# Peripherals.net
KiCad netlist of a schematic drawn in Altium Designer
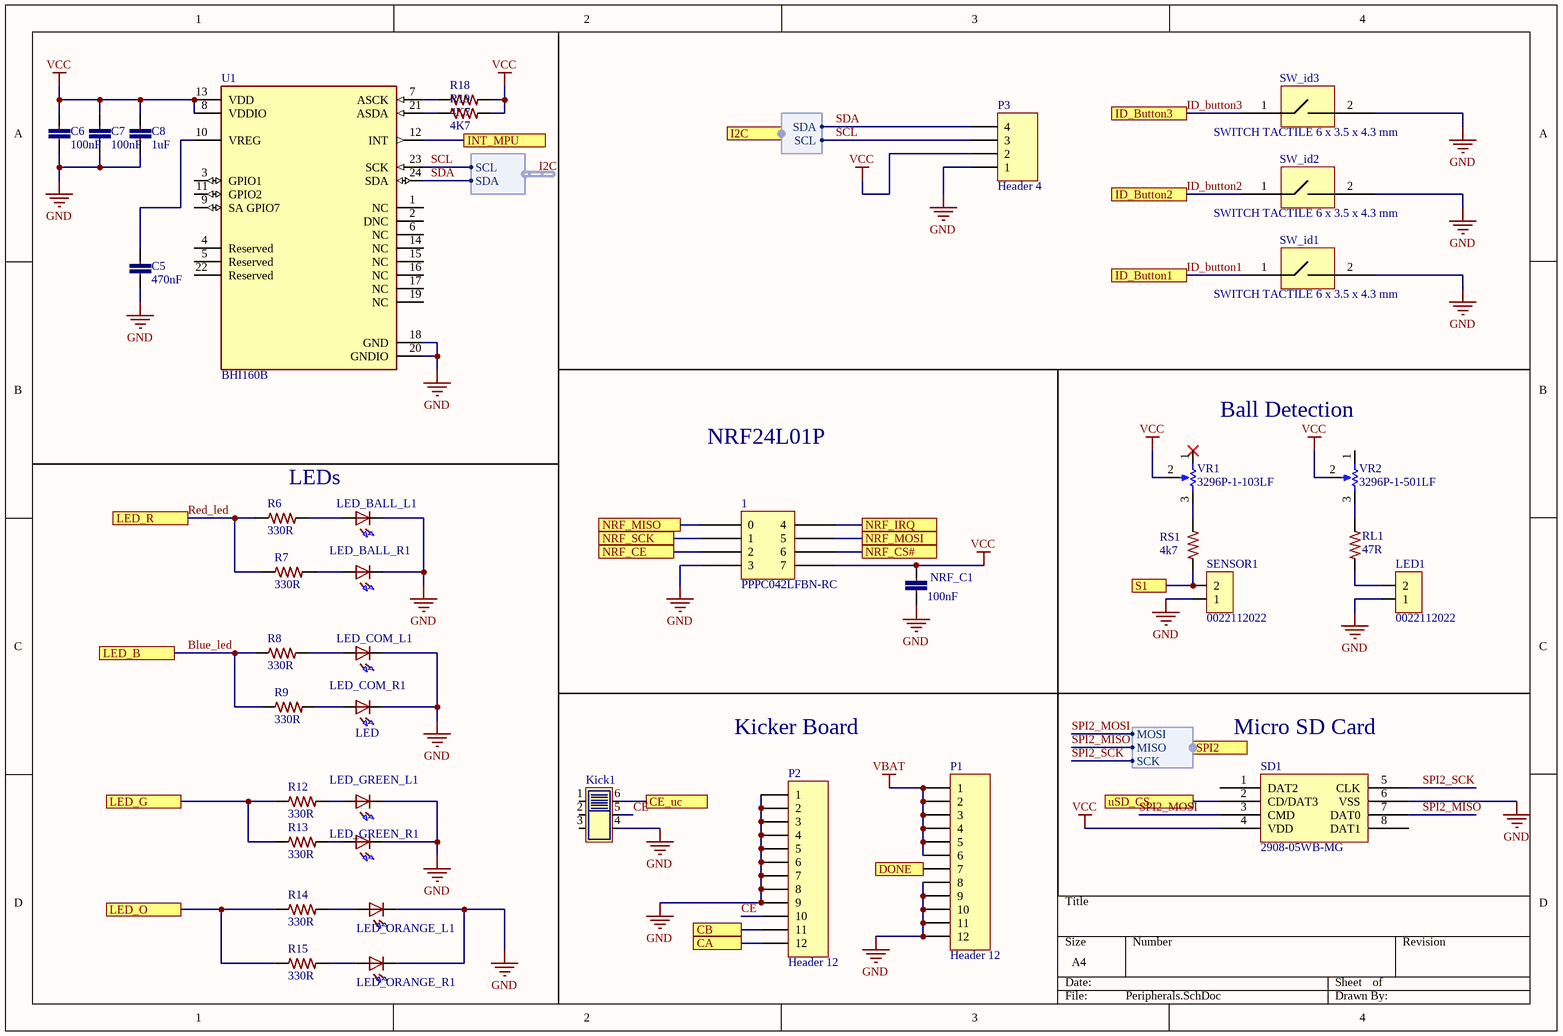
[diagram p0: Peripherals.SchDoc]

(export (version "E")
  (design (tool "Eeschema 10.0.6"))
  (components
    (comp (ref "1")
      (value "PPPC042LFBN-RC")
      (footprint "04x02_Conector_Female")
      (description "8 Position Header Connector 0.100\" (2.54mm) Through Hole Gold")
      (libsource (lib "Schlib1") (part "04x02_Conector_Female"))
    )
    (comp (ref "C5")
      (value "470nF")
      (footprint "0402-CAP")
      (description "CAP CER 0402 470nF 25V X5R")
      (fields (field (name "PART NO") "C1005X5R1E474K050"))
      (libsource (lib "IMBEL") (part "CAPACITOR"))
    )
    (comp (ref "C6")
      (value "100nF")
      (footprint "0402-CAP")
      (description "CAP CER 0.1UF 10V 20% X5R 0402")
      (fields (field (name "PART NO") "VJ0402V104ZXQPBC"))
      (libsource (lib "IMBEL") (part "CAPACITOR"))
    )
    (comp (ref "C7")
      (value "100nF")
      (footprint "0402-CAP")
      (description "CAP CER 0.1UF 10V 20% X5R 0402")
      (fields (field (name "PART NO") "VJ0402V104ZXQPBC"))
      (libsource (lib "IMBEL") (part "CAPACITOR"))
    )
    (comp (ref "C8")
      (value "1uF")
      (footprint "0402-CAP")
      (description "CAP CER 1UF 6.3V 10% X5R 0402")
      (fields (field (name "PART NO") "JMK105BJ105KV-F"))
      (libsource (lib "IMBEL") (part "CAPACITOR"))
    )
    (comp (ref "Kick1")
      (value "JS202011SCQN")
      (footprint "SOP250P750X350-6N")
      (description "SWITCH SLIDE DPDT 300MA 6V")
      (libsource (lib "") (part "Component_1_1"))
    )
    (comp (ref "LED1")
      (value "0022112022")
      (footprint "02x01_Conector_Male")
      (description "CONN HEADER 2POS .100 VERT GOLD")
      (libsource (lib "Schlib1") (part "02x01_Conector_Male"))
    )
    (comp (ref "LED_BALL_L1")
      (value "LED")
      (footprint "LED-5MM-PCB")
      (description "LED 5MM PTH")
      (libsource (lib "IMBEL") (part "LED"))
    )
    (comp (ref "LED_BALL_R1")
      (value "LED")
      (footprint "LED-5MM-PCB")
      (description "LED 5MM PTH")
      (libsource (lib "IMBEL") (part "LED"))
    )
    (comp (ref "LED_COM_L1")
      (value "LED")
      (footprint "LED-5MM-PCB")
      (description "LED 5MM PTH")
      (libsource (lib "IMBEL") (part "LED"))
    )
    (comp (ref "LED_COM_R1")
      (value "LED")
      (footprint "LED-5MM-PCB")
      (description "LED 5MM PTH")
      (libsource (lib "IMBEL") (part "LED"))
    )
    (comp (ref "LED_GREEN_L1")
      (value "LED")
      (footprint "LED-5MM-PCB")
      (description "LED 5MM PTH")
      (libsource (lib "IMBEL") (part "LED"))
    )
    (comp (ref "LED_GREEN_R1")
      (value "LED")
      (footprint "LED-5MM-PCB")
      (description "LED 5MM PTH")
      (libsource (lib "IMBEL") (part "LED"))
    )
    (comp (ref "LED_ORANGE_L1")
      (value "LED")
      (footprint "LED-5MM-PCB")
      (description "LED 5MM PTH")
      (libsource (lib "IMBEL") (part "LED"))
    )
    (comp (ref "LED_ORANGE_R1")
      (value "LED")
      (footprint "LED-5MM-PCB")
      (description "LED 5MM PTH")
      (libsource (lib "IMBEL") (part "LED"))
    )
    (comp (ref "NRF_C1")
      (value "100nF")
      (footprint "0402-CAP")
      (description "CAP CER 0.1UF 10V 20% X5R 0402")
      (fields (field (name "PART NO") "VJ0402V104ZXQPBC"))
      (libsource (lib "IMBEL") (part "CC0402-100nF-A.12"))
    )
    (comp (ref "P1")
      (value "Header 12")
      (footprint "HDR1X12")
      (description "Header, 12-Pin")
      (fields (field (name "PUBLISHER") "Altium Limited"))
      (libsource (lib "Miscellaneous Connectors") (part "Header 12"))
    )
    (comp (ref "P2")
      (value "Header 12")
      (footprint "HDR1X12")
      (description "Header, 12-Pin")
      (fields (field (name "PUBLISHER") "Altium Limited"))
      (libsource (lib "Miscellaneous Connectors") (part "Header 12"))
    )
    (comp (ref "P3")
      (value "Header 4")
      (footprint "HDR1X4")
      (description "Header, 4-Pin")
      (fields (field (name "PUBLISHER") "Altium Limited"))
      (libsource (lib "Miscellaneous Connectors") (part "Header 4"))
    )
    (comp (ref "R6")
      (value "330R")
      (footprint "0402-RES-HD")
      (description "RES 330 OHM 1/10W 1% 0402 SMD")
      (fields (field (name "PART NO") "ERJ-2RKF3300X"))
      (libsource (lib "IMBEL") (part "RESISTOR"))
    )
    (comp (ref "R7")
      (value "330R")
      (footprint "0402-RES-HD")
      (description "RES 330 OHM 1/10W 1% 0402 SMD")
      (fields (field (name "PART NO") "ERJ-2RKF3300X"))
      (libsource (lib "IMBEL") (part "RESISTOR"))
    )
    (comp (ref "R8")
      (value "330R")
      (footprint "0402-RES-HD")
      (description "RES 330 OHM 1/10W 1% 0402 SMD")
      (fields (field (name "PART NO") "ERJ-2RKF3300X"))
      (libsource (lib "IMBEL") (part "RESISTOR"))
    )
    (comp (ref "R9")
      (value "330R")
      (footprint "0402-RES-HD")
      (description "RES 330 OHM 1/10W 1% 0402 SMD")
      (fields (field (name "PART NO") "ERJ-2RKF3300X"))
      (libsource (lib "IMBEL") (part "RESISTOR"))
    )
    (comp (ref "R12")
      (value "330R")
      (footprint "0402-RES-HD")
      (description "RES 330 OHM 1/10W 1% 0402 SMD")
      (fields (field (name "PART NO") "ERJ-2RKF3300X"))
      (libsource (lib "IMBEL") (part "RESISTOR"))
    )
    (comp (ref "R13")
      (value "330R")
      (footprint "0402-RES-HD")
      (description "RES 330 OHM 1/10W 1% 0402 SMD")
      (fields (field (name "PART NO") "ERJ-2RKF3300X"))
      (libsource (lib "IMBEL") (part "RESISTOR"))
    )
    (comp (ref "R14")
      (value "330R")
      (footprint "0402-RES-HD")
      (description "RES 330 OHM 1/10W 1% 0402 SMD")
      (fields (field (name "PART NO") "ERJ-2RKF3300X"))
      (libsource (lib "IMBEL") (part "RESISTOR"))
    )
    (comp (ref "R15")
      (value "330R")
      (footprint "0402-RES-HD")
      (description "RES 330 OHM 1/10W 1% 0402 SMD")
      (fields (field (name "PART NO") "ERJ-2RKF3300X"))
      (libsource (lib "IMBEL") (part "RESISTOR"))
    )
    (comp (ref "R18")
      (value "4K7")
      (footprint "0805-RES")
      (description "RES SMD 4.7K OHM 1% 1/8W 0805")
      (fields (field (name "PART NO") "CRCW08054K70FKEA"))
      (libsource (lib "IMBEL") (part "RESISTOR"))
    )
    (comp (ref "R19")
      (value "4K7")
      (footprint "0805-RES")
      (description "RES SMD 4.7K OHM 1% 1/8W 0805")
      (fields (field (name "PART NO") "CRCW08054K70FKEA"))
      (libsource (lib "IMBEL") (part "RESISTOR"))
    )
    (comp (ref "RL1")
      (value "47R")
      (footprint "0402-RES-HD")
      (description "RES 47 OHM 1/10W 1% 0402 SMD")
      (fields (field (name "PART NO") "ERJ-2RKF1000X"))
      (libsource (lib "IMBEL") (part "RESISTOR"))
    )
    (comp (ref "RS1")
      (value "4k7")
      (footprint "0402-RES-HD")
      (description "RES 4k7 OHM 1/10W 1% 0402 SMD")
      (fields (field (name "PART NO") "ERJ-2RKF3300X"))
      (libsource (lib "IMBEL") (part "RESISTOR"))
    )
    (comp (ref "SD1")
      (value "2908-05WB-MG")
      (footprint "New footprint 1")
      (description "CONN MICRO SD CARD PUSH-PUSH R/A")
      (libsource (lib "IMBEL") (part "SD-CON-SCH"))
    )
    (comp (ref "SENSOR1")
      (value "0022112022")
      (footprint "02x01_Conector_Male")
      (description "CONN HEADER 2POS .100 VERT GOLD")
      (libsource (lib "Schlib1") (part "02x01_Conector_Male"))
    )
    (comp (ref "SW_id1")
      (value "SWITCH TACTILE 6 x 3.5 x 4.3 mm")
      (footprint "PCBComponent")
      (description "GRAYHILL TACT,GW,6X3.5,1800T&R,LF Eight, 160g Operating Force, Gull Wing, RoHS Compliant")
      (fields (field (name "PART NO") "95C04A3GWRT"))
      (libsource (lib "IMBEL") (part "Component_1"))
    )
    (comp (ref "SW_id2")
      (value "SWITCH TACTILE 6 x 3.5 x 4.3 mm")
      (footprint "PCBComponent")
      (description "GRAYHILL TACT,GW,6X3.5,1800T&R,LF Eight, 160g Operating Force, Gull Wing, RoHS Compliant")
      (fields (field (name "PART NO") "95C04A3GWRT"))
      (libsource (lib "IMBEL") (part "Component_1"))
    )
    (comp (ref "SW_id3")
      (value "SWITCH TACTILE 6 x 3.5 x 4.3 mm")
      (footprint "PCBComponent")
      (description "GRAYHILL TACT,GW,6X3.5,1800T&R,LF Eight, 160g Operating Force, Gull Wing, RoHS Compliant")
      (fields (field (name "PART NO") "95C04A3GWRT"))
      (libsource (lib "IMBEL") (part "Component_1"))
    )
    (comp (ref "U1")
      (value "BHI160B")
      (footprint "FP-BHI160B-MFG")
      (description "IMU ACCEL/GYRO 3-AXIS I2C 24LGA")
      (fields
        (field (name "OCTOPART") "https://octopart.com/bhi160b-bosch+sensortec-108216126")
        (field (name "MANUFACTURER") "Bosch Sensortec")
      )
      (libsource (lib "Altium Content Vault") (part "2d8cd2e68e3e323d24208bb39551349"))
    )
    (comp (ref "VR1")
      (value "3296P-1-103LF")
      (footprint "pcblib1:3296P")
      (description "Trimmer;  Cermet;  Rest 10 Kilohms;  PCB;  25 Turns;  Pwr-Rtg 0.5W")
      (fields (field (name "MANUFACTURER") "Bourns") (field (name "TOLERANCE") "10%"))
      (libsource (lib "Schlib1") (part "3296P-1-103LF"))
    )
    (comp (ref "VR2")
      (value "3296P-1-501LF")
      (footprint "PcbLib1:3296P")
      (description "Res Cermet Trimmer 500 Ohm 10% 1/2W 25(Elec)Turn 2.19mm (9.53 X 11.55 X 4.83mm) Pin Thru-Hole Tube")
      (fields (field (name "MANUFACTURER") "Bourns") (field (name "TOLERANCE") "10%"))
      (libsource (lib "Schlib1") (part "3296P-1-501LF"))
    )
  )
  (nets
    (net (code "4") (name "/Blue_led") (class "Default")
      (node (ref "R8") (pin "1") (pinfunction "1_1") (pintype "passive"))
      (node (ref "R9") (pin "1") (pinfunction "1_1") (pintype "passive"))
    )
    (net (code "5") (name "/CA") (class "Default")
      (node (ref "P2") (pin "12") (pinfunction "12_12") (pintype "passive"))
    )
    (net (code "6") (name "/CB") (class "Default")
      (node (ref "P2") (pin "11") (pinfunction "11_11") (pintype "passive"))
    )
    (net (code "7") (name "/CE") (class "Default")
      (node (ref "Kick1") (pin "5") (pintype "passive"))
      (node (ref "P2") (pin "10") (pinfunction "10_10") (pintype "passive"))
    )
    (net (code "8") (name "/CE_uc") (class "Default") (node (ref "Kick1") (pin "6") (pintype "passive")))
    (net (code "9") (name "/DONE") (class "Default")
      (node (ref "P1") (pin "7") (pinfunction "7_7") (pintype "passive"))
    )
    (net (code "11") (name "/ID_button1") (class "Default")
      (node (ref "SW_id1") (pin "1") (pinfunction "1_1") (pintype "passive"))
    )
    (net (code "12") (name "/ID_button2") (class "Default")
      (node (ref "SW_id2") (pin "1") (pinfunction "1_1") (pintype "passive"))
    )
    (net (code "13") (name "/ID_button3") (class "Default")
      (node (ref "SW_id3") (pin "1") (pinfunction "1_1") (pintype "passive"))
    )
    (net (code "14") (name "/INT_MPU") (class "Default")
      (node (ref "U1") (pin "12") (pinfunction "INT_12") (pintype "output"))
    )
    (net (code "15") (name "/LED_G") (class "Default")
      (node (ref "R12") (pin "1") (pinfunction "1_1") (pintype "passive"))
      (node (ref "R13") (pin "1") (pinfunction "1_1") (pintype "passive"))
    )
    (net (code "16") (name "/LED_O") (class "Default")
      (node (ref "R14") (pin "1") (pinfunction "1_1") (pintype "passive"))
      (node (ref "R15") (pin "1") (pinfunction "1_1") (pintype "passive"))
    )
    (net (code "17") (name "/NRF_CE") (class "Default")
      (node (ref "1") (pin "2") (pinfunction "2_2") (pintype "passive"))
    )
    (net (code "18") (name "/NRF_CS#") (class "Default")
      (node (ref "1") (pin "6") (pinfunction "6_6") (pintype "passive"))
    )
    (net (code "19") (name "/NRF_IRQ") (class "Default")
      (node (ref "1") (pin "4") (pinfunction "4_4") (pintype "passive"))
    )
    (net (code "20") (name "/NRF_MISO") (class "Default")
      (node (ref "1") (pin "0") (pinfunction "0_0") (pintype "passive"))
    )
    (net (code "21") (name "/NRF_MOSI") (class "Default")
      (node (ref "1") (pin "5") (pinfunction "5_5") (pintype "passive"))
    )
    (net (code "22") (name "/NRF_SCK") (class "Default")
      (node (ref "1") (pin "1") (pinfunction "1_1") (pintype "passive"))
    )
    (net (code "23") (name "/Red_led") (class "Default")
      (node (ref "R6") (pin "1") (pinfunction "1_1") (pintype "passive"))
      (node (ref "R7") (pin "1") (pinfunction "1_1") (pintype "passive"))
    )
    (net (code "24") (name "/S1") (class "Default")
      (node (ref "RS1") (pin "1") (pinfunction "1_1") (pintype "passive"))
      (node (ref "SENSOR1") (pin "2") (pinfunction "2_2") (pintype "passive"))
    )
    (net (code "25") (name "/SCL") (class "Default")
      (node (ref "P3") (pin "3") (pinfunction "3_3") (pintype "passive"))
      (node (ref "U1") (pin "23") (pinfunction "SCK_23") (pintype "input"))
    )
    (net (code "26") (name "/SDA") (class "Default")
      (node (ref "P3") (pin "4") (pinfunction "4_4") (pintype "passive"))
      (node (ref "U1") (pin "24") (pinfunction "SDA_24") (pintype "bidirectional"))
    )
    (net (code "27") (name "/SPI2_MISO") (class "Default")
      (node (ref "SD1") (pin "7") (pinfunction "DAT0_7") (pintype "passive"))
    )
    (net (code "28") (name "/SPI2_MOSI") (class "Default")
      (node (ref "SD1") (pin "3") (pinfunction "CMD_3") (pintype "passive"))
    )
    (net (code "29") (name "/SPI2_SCK") (class "Default")
      (node (ref "SD1") (pin "5") (pinfunction "CLK_5") (pintype "passive"))
    )
    (net (code "30") (name "/uSD_CS") (class "Default")
      (node (ref "SD1") (pin "2") (pinfunction "CD/DAT3_2") (pintype "passive"))
    )
    (net (code "32") (name "GND") (class "Default")
      (node (ref "1") (pin "3") (pinfunction "3_3") (pintype "passive"))
      (node (ref "C5") (pin "2") (pinfunction "2_2") (pintype "passive"))
      (node (ref "C6") (pin "2") (pinfunction "2_2") (pintype "passive"))
      (node (ref "C7") (pin "2") (pinfunction "2_2") (pintype "passive"))
      (node (ref "C8") (pin "2") (pinfunction "2_2") (pintype "passive"))
      (node (ref "Kick1") (pin "4") (pintype "passive"))
      (node (ref "LED1") (pin "1") (pinfunction "1_1") (pintype "passive"))
      (node (ref "LED_BALL_L1") (pin "1") (pinfunction "K_1") (pintype "passive"))
      (node (ref "LED_BALL_R1") (pin "1") (pinfunction "K_1") (pintype "passive"))
      (node (ref "LED_COM_L1") (pin "1") (pinfunction "K_1") (pintype "passive"))
      (node (ref "LED_COM_R1") (pin "1") (pinfunction "K_1") (pintype "passive"))
      (node (ref "LED_GREEN_L1") (pin "1") (pinfunction "K_1") (pintype "passive"))
      (node (ref "LED_GREEN_R1") (pin "1") (pinfunction "K_1") (pintype "passive"))
      (node (ref "LED_ORANGE_L1") (pin "1") (pinfunction "K_1") (pintype "passive"))
      (node (ref "LED_ORANGE_R1") (pin "1") (pinfunction "K_1") (pintype "passive"))
      (node (ref "NRF_C1") (pin "2") (pinfunction "2_2") (pintype "passive"))
      (node (ref "P1") (pin "10") (pinfunction "10_10") (pintype "passive"))
      (node (ref "P1") (pin "11") (pinfunction "11_11") (pintype "passive"))
      (node (ref "P1") (pin "12") (pinfunction "12_12") (pintype "passive"))
      (node (ref "P1") (pin "8") (pinfunction "8_8") (pintype "passive"))
      (node (ref "P1") (pin "9") (pinfunction "9_9") (pintype "passive"))
      (node (ref "P2") (pin "1") (pinfunction "1_1") (pintype "passive"))
      (node (ref "P2") (pin "2") (pinfunction "2_2") (pintype "passive"))
      (node (ref "P2") (pin "3") (pinfunction "3_3") (pintype "passive"))
      (node (ref "P2") (pin "4") (pinfunction "4_4") (pintype "passive"))
      (node (ref "P2") (pin "5") (pinfunction "5_5") (pintype "passive"))
      (node (ref "P2") (pin "6") (pinfunction "6_6") (pintype "passive"))
      (node (ref "P2") (pin "7") (pinfunction "7_7") (pintype "passive"))
      (node (ref "P2") (pin "8") (pinfunction "8_8") (pintype "passive"))
      (node (ref "P2") (pin "9") (pinfunction "9_9") (pintype "passive"))
      (node (ref "P3") (pin "1") (pinfunction "1_1") (pintype "passive"))
      (node (ref "SD1") (pin "6") (pinfunction "VSS_6") (pintype "passive"))
      (node (ref "SENSOR1") (pin "1") (pinfunction "1_1") (pintype "passive"))
      (node (ref "SW_id1") (pin "2") (pinfunction "2_2") (pintype "passive"))
      (node (ref "SW_id2") (pin "2") (pinfunction "2_2") (pintype "passive"))
      (node (ref "SW_id3") (pin "2") (pinfunction "2_2") (pintype "passive"))
      (node (ref "U1") (pin "18") (pinfunction "GND_18") (pintype "power_in"))
      (node (ref "U1") (pin "20") (pinfunction "GNDIO_20") (pintype "power_in"))
    )
    (net (code "33") (name "Net-(LED1-Pad2)") (class "Default")
      (node (ref "LED1") (pin "2") (pinfunction "2_2") (pintype "passive"))
      (node (ref "RL1") (pin "2") (pinfunction "2_2") (pintype "passive"))
    )
    (net (code "34") (name "Net-(LED_BALL_L1-A)") (class "Default")
      (node (ref "LED_BALL_L1") (pin "2") (pinfunction "A_2") (pintype "passive"))
      (node (ref "R6") (pin "2") (pinfunction "2_2") (pintype "passive"))
    )
    (net (code "35") (name "Net-(LED_BALL_R1-A)") (class "Default")
      (node (ref "LED_BALL_R1") (pin "2") (pinfunction "A_2") (pintype "passive"))
      (node (ref "R7") (pin "2") (pinfunction "2_2") (pintype "passive"))
    )
    (net (code "36") (name "Net-(LED_COM_L1-A)") (class "Default")
      (node (ref "LED_COM_L1") (pin "2") (pinfunction "A_2") (pintype "passive"))
      (node (ref "R8") (pin "2") (pinfunction "2_2") (pintype "passive"))
    )
    (net (code "37") (name "Net-(LED_COM_R1-A)") (class "Default")
      (node (ref "LED_COM_R1") (pin "2") (pinfunction "A_2") (pintype "passive"))
      (node (ref "R9") (pin "2") (pinfunction "2_2") (pintype "passive"))
    )
    (net (code "38") (name "Net-(LED_GREEN_L1-A)") (class "Default")
      (node (ref "LED_GREEN_L1") (pin "2") (pinfunction "A_2") (pintype "passive"))
      (node (ref "R12") (pin "2") (pinfunction "2_2") (pintype "passive"))
    )
    (net (code "39") (name "Net-(LED_GREEN_R1-A)") (class "Default")
      (node (ref "LED_GREEN_R1") (pin "2") (pinfunction "A_2") (pintype "passive"))
      (node (ref "R13") (pin "2") (pinfunction "2_2") (pintype "passive"))
    )
    (net (code "40") (name "Net-(LED_ORANGE_L1-A)") (class "Default")
      (node (ref "LED_ORANGE_L1") (pin "2") (pinfunction "A_2") (pintype "passive"))
      (node (ref "R14") (pin "2") (pinfunction "2_2") (pintype "passive"))
    )
    (net (code "41") (name "Net-(LED_ORANGE_R1-A)") (class "Default")
      (node (ref "LED_ORANGE_R1") (pin "2") (pinfunction "A_2") (pintype "passive"))
      (node (ref "R15") (pin "2") (pinfunction "2_2") (pintype "passive"))
    )
    (net (code "42") (name "Net-(U1-ASCK)") (class "Default")
      (node (ref "R18") (pin "1") (pinfunction "1_1") (pintype "passive"))
      (node (ref "U1") (pin "7") (pinfunction "ASCK_7") (pintype "input"))
    )
    (net (code "43") (name "Net-(U1-ASDA)") (class "Default")
      (node (ref "R19") (pin "1") (pinfunction "1_1") (pintype "passive"))
      (node (ref "U1") (pin "21") (pinfunction "ASDA_21") (pintype "input"))
    )
    (net (code "44") (name "Net-(U1-VREG)") (class "Default")
      (node (ref "C5") (pin "1") (pinfunction "1_1") (pintype "passive"))
      (node (ref "U1") (pin "10") (pinfunction "VREG_10") (pintype "passive"))
    )
    (net (code "45") (name "Net-(VR1-CW)") (class "Default")
      (node (ref "RS1") (pin "2") (pinfunction "2_2") (pintype "passive"))
      (node (ref "VR1") (pin "3") (pinfunction "CW_3") (pintype "passive"))
    )
    (net (code "46") (name "Net-(VR2-CW)") (class "Default")
      (node (ref "RL1") (pin "1") (pinfunction "1_1") (pintype "passive"))
      (node (ref "VR2") (pin "3") (pinfunction "CW_3") (pintype "passive"))
    )
    (net (code "47") (name "VBAT") (class "Default")
      (node (ref "P1") (pin "1") (pinfunction "1_1") (pintype "passive"))
      (node (ref "P1") (pin "2") (pinfunction "2_2") (pintype "passive"))
      (node (ref "P1") (pin "3") (pinfunction "3_3") (pintype "passive"))
      (node (ref "P1") (pin "4") (pinfunction "4_4") (pintype "passive"))
      (node (ref "P1") (pin "5") (pinfunction "5_5") (pintype "passive"))
      (node (ref "P1") (pin "6") (pinfunction "6_6") (pintype "passive"))
    )
    (net (code "48") (name "VCC") (class "Default")
      (node (ref "1") (pin "7") (pinfunction "7_7") (pintype "passive"))
      (node (ref "C6") (pin "1") (pinfunction "1_1") (pintype "passive"))
      (node (ref "C7") (pin "1") (pinfunction "1_1") (pintype "passive"))
      (node (ref "C8") (pin "1") (pinfunction "1_1") (pintype "passive"))
      (node (ref "NRF_C1") (pin "1") (pinfunction "1_1") (pintype "passive"))
      (node (ref "P3") (pin "2") (pinfunction "2_2") (pintype "passive"))
      (node (ref "R18") (pin "2") (pinfunction "2_2") (pintype "passive"))
      (node (ref "R19") (pin "2") (pinfunction "2_2") (pintype "passive"))
      (node (ref "SD1") (pin "4") (pinfunction "VDD_4") (pintype "passive"))
      (node (ref "U1") (pin "13") (pinfunction "VDD_13") (pintype "power_in"))
      (node (ref "U1") (pin "8") (pinfunction "VDDIO_8") (pintype "power_in"))
      (node (ref "VR1") (pin "2") (pinfunction "Wiper_2") (pintype "passive"))
      (node (ref "VR2") (pin "2") (pinfunction "Wiper_2") (pintype "passive"))
    )
    (net (code "49") (name "unconnected-(Kick1-Pad1)") (class "Default")
      (node (ref "Kick1") (pin "1") (pintype "passive"))
    )
    (net (code "50") (name "unconnected-(Kick1-Pad2)") (class "Default")
      (node (ref "Kick1") (pin "2") (pintype "passive"))
    )
    (net (code "51") (name "unconnected-(Kick1-Pad3)") (class "Default")
      (node (ref "Kick1") (pin "3") (pintype "passive"))
    )
    (net (code "52") (name "unconnected-(SD1-DAT1-Pad8)") (class "Default")
      (node (ref "SD1") (pin "8") (pinfunction "DAT1_8") (pintype "passive"))
    )
    (net (code "53") (name "unconnected-(SD1-DAT2-Pad1)") (class "Default")
      (node (ref "SD1") (pin "1") (pinfunction "DAT2_1") (pintype "passive"))
    )
    (net (code "54") (name "unconnected-(U1-DNC-Pad2)") (class "Default")
      (node (ref "U1") (pin "2") (pinfunction "DNC_2") (pintype "passive"))
    )
    (net (code "55") (name "unconnected-(U1-GPIO1-Pad3)") (class "Default")
      (node (ref "U1") (pin "3") (pinfunction "GPIO1_3") (pintype "bidirectional"))
    )
    (net (code "56") (name "unconnected-(U1-GPIO2-Pad11)") (class "Default")
      (node (ref "U1") (pin "11") (pinfunction "GPIO2_11") (pintype "bidirectional"))
    )
    (net (code "57") (name "unconnected-(U1-NC-Pad1)") (class "Default")
      (node (ref "U1") (pin "1") (pinfunction "NC_1") (pintype "passive"))
    )
    (net (code "58") (name "unconnected-(U1-NC-Pad6)") (class "Default")
      (node (ref "U1") (pin "6") (pinfunction "NC_6") (pintype "passive"))
    )
    (net (code "59") (name "unconnected-(U1-NC-Pad14)") (class "Default")
      (node (ref "U1") (pin "14") (pinfunction "NC_14") (pintype "passive"))
    )
    (net (code "60") (name "unconnected-(U1-NC-Pad15)") (class "Default")
      (node (ref "U1") (pin "15") (pinfunction "NC_15") (pintype "passive"))
    )
    (net (code "61") (name "unconnected-(U1-NC-Pad16)") (class "Default")
      (node (ref "U1") (pin "16") (pinfunction "NC_16") (pintype "passive"))
    )
    (net (code "62") (name "unconnected-(U1-NC-Pad17)") (class "Default")
      (node (ref "U1") (pin "17") (pinfunction "NC_17") (pintype "passive"))
    )
    (net (code "63") (name "unconnected-(U1-NC-Pad19)") (class "Default")
      (node (ref "U1") (pin "19") (pinfunction "NC_19") (pintype "passive"))
    )
    (net (code "64") (name "unconnected-(U1-Reserved-Pad4)") (class "Default")
      (node (ref "U1") (pin "4") (pinfunction "Reserved_4") (pintype "passive"))
    )
    (net (code "65") (name "unconnected-(U1-Reserved-Pad5)") (class "Default")
      (node (ref "U1") (pin "5") (pinfunction "Reserved_5") (pintype "passive"))
    )
    (net (code "66") (name "unconnected-(U1-Reserved-Pad22)") (class "Default")
      (node (ref "U1") (pin "22") (pinfunction "Reserved_22") (pintype "passive"))
    )
    (net (code "67") (name "unconnected-(U1-SA_GPIO7-Pad9)") (class "Default")
      (node (ref "U1") (pin "9") (pinfunction "SA_GPIO7_9") (pintype "bidirectional"))
    )
    (net (code "68") (name "unconnected-(VR1-CCW-Pad1)") (class "Default")
      (node (ref "VR1") (pin "1") (pinfunction "CCW_1") (pintype "passive+no_connect"))
    )
    (net (code "69") (name "unconnected-(VR2-CCW-Pad1)") (class "Default")
      (node (ref "VR2") (pin "1") (pinfunction "CCW_1") (pintype "passive"))
    )
  )
)
